# Sheet1.net
KiCad netlist of a schematic drawn in Altium Designer
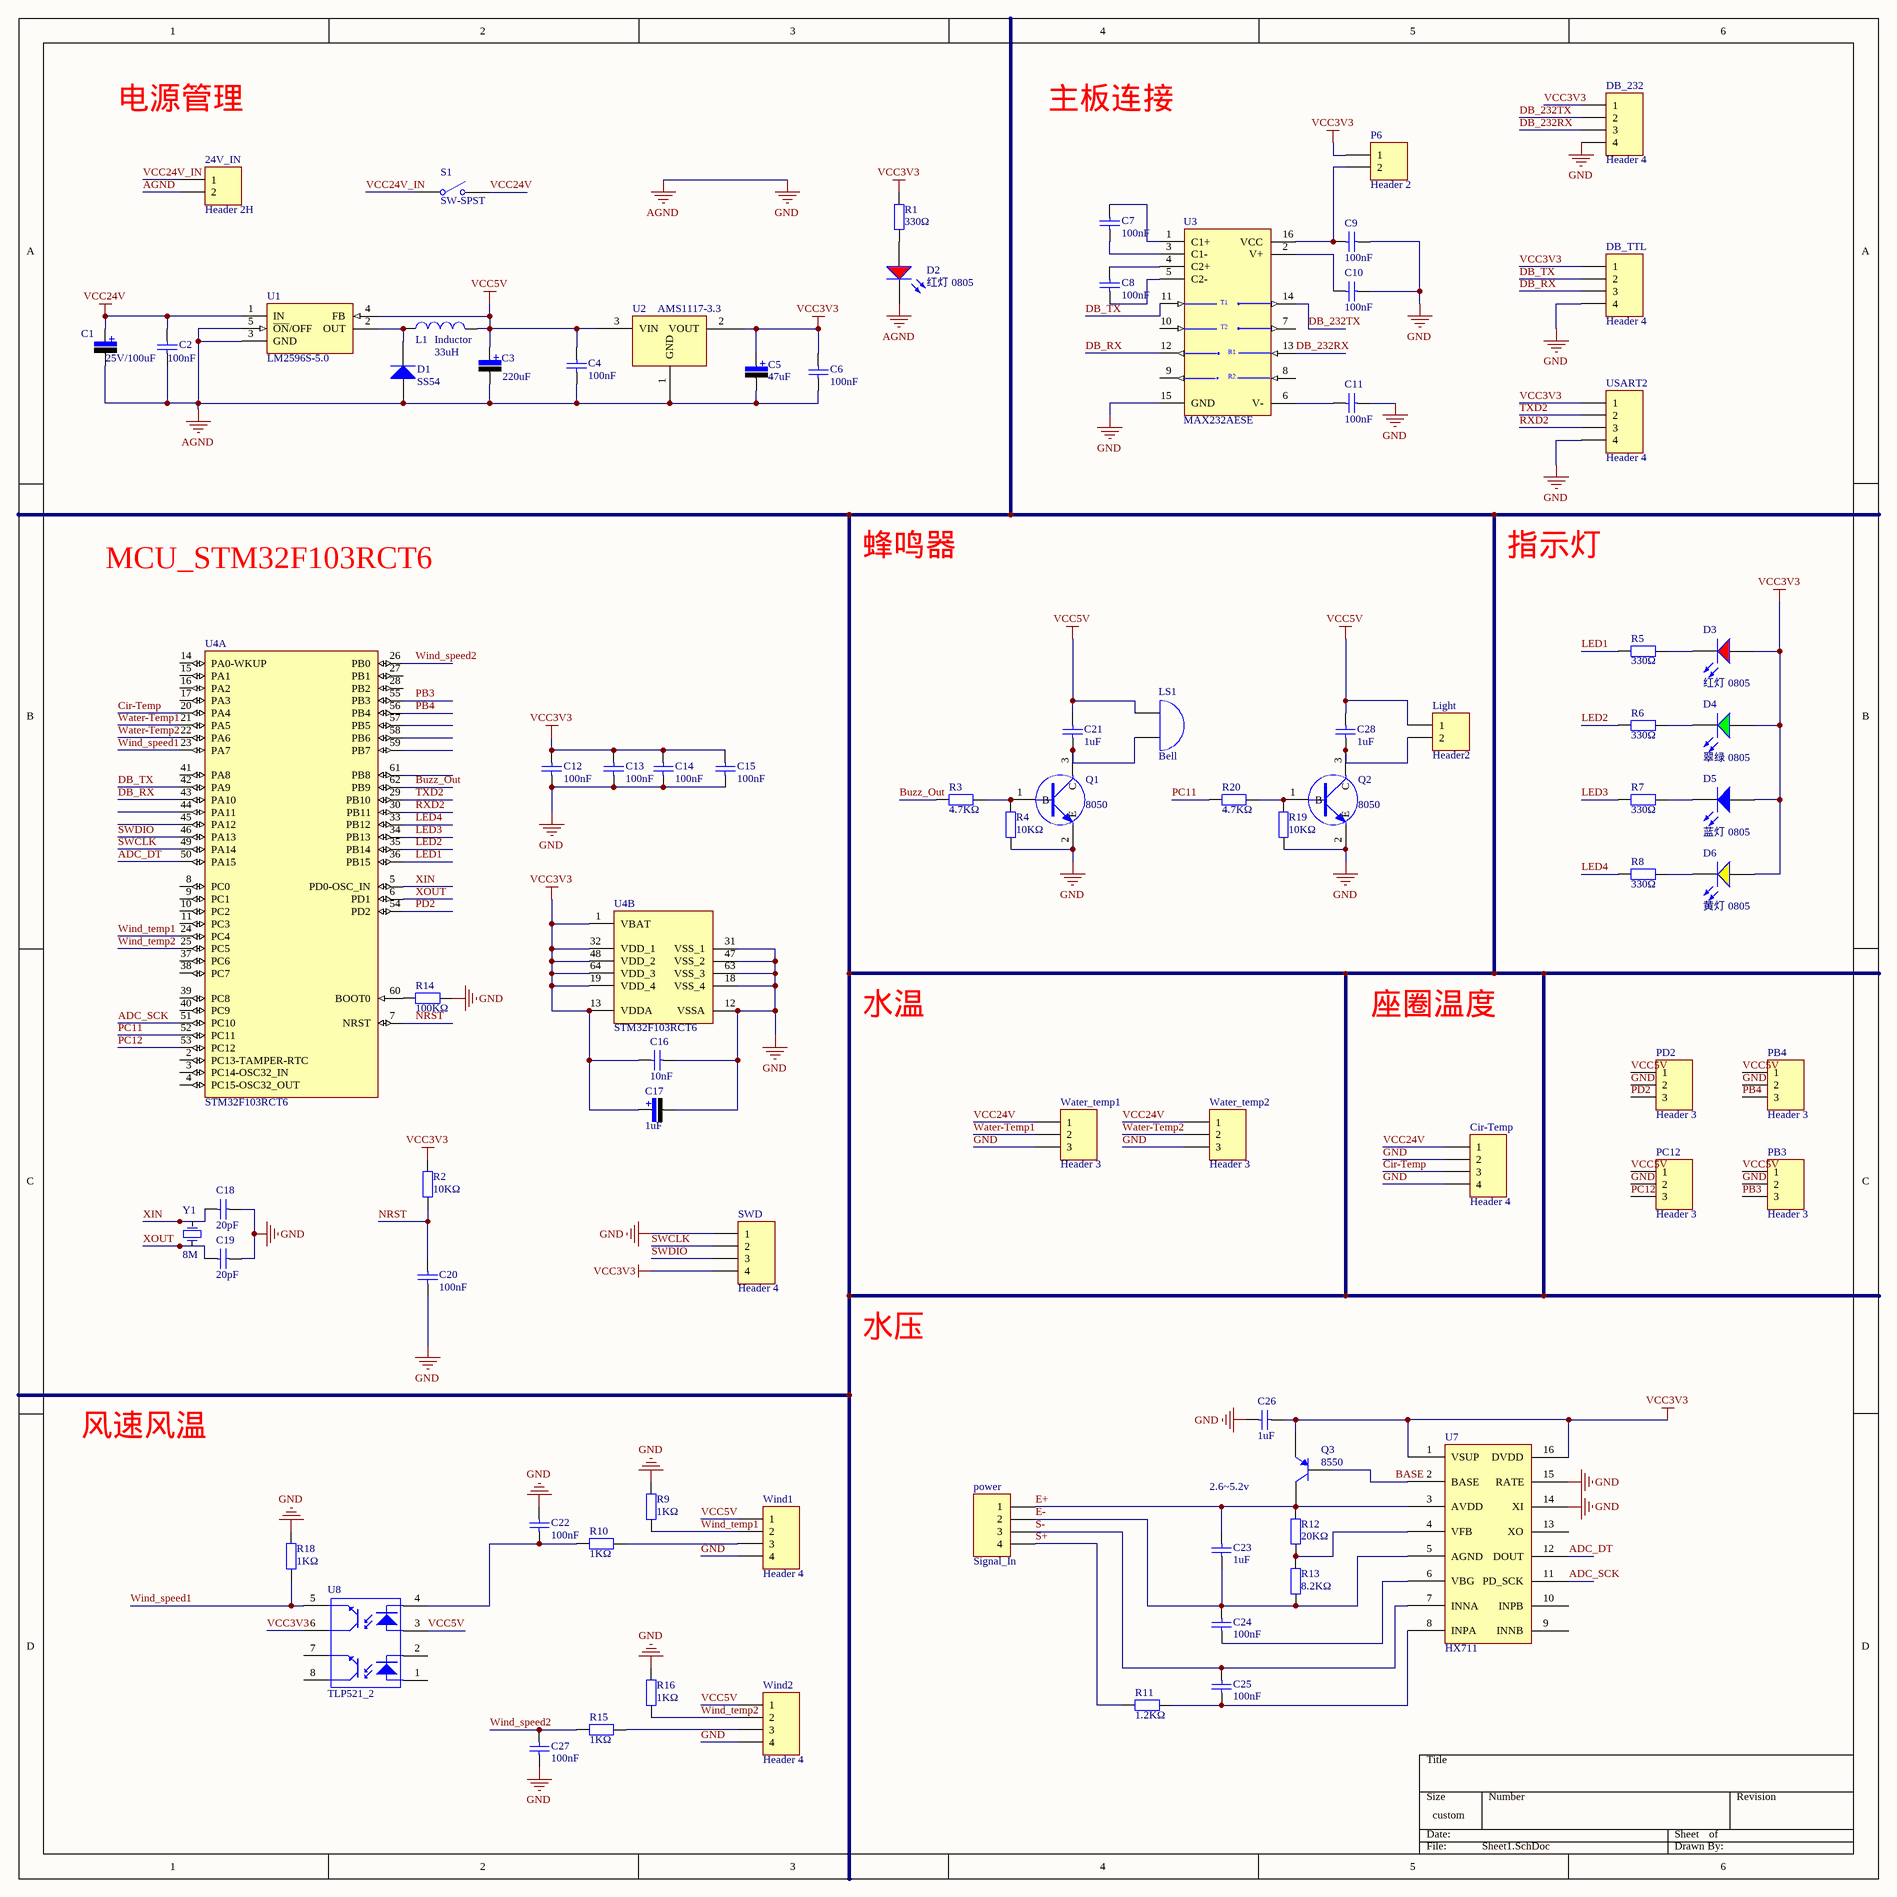
[diagram p0: Sheet1.SchDoc]

(export (version "E")
  (design (tool "Eeschema 10.0.6"))
  (components
    (comp (ref "24V_IN")
      (value "Header 2H")
      (footprint "4.2mm接插件2P")
      (description "Header, 2-Pin, Right Angle")
      (fields (field (name "PUBLISHER") "Altium Limited"))
      (libsource (lib "Miscellaneous Connectors") (part "Header 2H"))
    )
    (comp (ref "C1")
      (value "25V/100uF")
      (footprint "CC6.56.5")
      (description "极性电解电容")
      (fields (field (name "Comment") "Cap Pol") (field (name "PUBLISHER") "Altium Limited"))
      (libsource (lib "Cycle ergometer") (part "Cap Pol"))
    )
    (comp (ref "C2")
      (value "100nF")
      (footprint "0805_C")
      (description "贴片电容")
      (libsource (lib "Cap") (part "0805 100nF(104) 10% 50V"))
    )
    (comp (ref "C3")
      (value "220uF")
      (footprint "CC6.56.5")
      (description "极性电解电容")
      (fields (field (name "Comment") "Cap Pol") (field (name "PUBLISHER") "Altium Limited"))
      (libsource (lib "Cycle ergometer") (part "Cap Pol"))
    )
    (comp (ref "C4")
      (value "100nF")
      (footprint "0805_C")
      (description "贴片电容")
      (libsource (lib "Cap") (part "0805 100nF(104) 10% 50V"))
    )
    (comp (ref "C5")
      (value "47uF")
      (footprint "贴片电容5*5.4")
      (description "极性电解电容")
      (fields (field (name "Comment") "Cap Pol") (field (name "PUBLISHER") "Altium Limited"))
      (libsource (lib "Cycle ergometer") (part "Cap Pol"))
    )
    (comp (ref "C6")
      (value "100nF")
      (footprint "0805_C")
      (description "贴片电容")
      (libsource (lib "Cap") (part "0805 100nF(104) 10% 50V"))
    )
    (comp (ref "C7")
      (value "100nF")
      (footprint "0805_C")
      (description "贴片电容")
      (libsource (lib "Cap") (part "0805 100nF(104) 10% 50V"))
    )
    (comp (ref "C8")
      (value "100nF")
      (footprint "0805_C")
      (description "贴片电容")
      (libsource (lib "Cap") (part "0805 100nF(104) 10% 50V"))
    )
    (comp (ref "C9")
      (value "100nF")
      (footprint "0805_C")
      (description "贴片电容")
      (libsource (lib "Cap") (part "0805 100nF(104) 10% 50V"))
    )
    (comp (ref "C10")
      (value "100nF")
      (footprint "0805_C")
      (description "贴片电容")
      (libsource (lib "Cap") (part "0805 100nF(104) 10% 50V"))
    )
    (comp (ref "C11")
      (value "100nF")
      (footprint "0805_C")
      (description "贴片电容")
      (libsource (lib "Cap") (part "0805 100nF(104) 10% 50V"))
    )
    (comp (ref "C12")
      (value "100nF")
      (footprint "0805_C")
      (description "贴片电容")
      (libsource (lib "Cap") (part "0805 100nF(104) 10% 50V"))
    )
    (comp (ref "C13")
      (value "100nF")
      (footprint "0805_C")
      (description "贴片电容")
      (libsource (lib "Cap") (part "0805 100nF(104) 10% 50V"))
    )
    (comp (ref "C14")
      (value "100nF")
      (footprint "0805_C")
      (description "贴片电容")
      (libsource (lib "Cap") (part "0805 100nF(104) 10% 50V"))
    )
    (comp (ref "C15")
      (value "100nF")
      (footprint "0805_C")
      (description "贴片电容")
      (libsource (lib "Cap") (part "0805 100nF(104) 10% 50V"))
    )
    (comp (ref "C16")
      (value "10nF")
      (footprint "0805_C")
      (description "贴片电容")
      (libsource (lib "Cap") (part "0805 10nF (103) 10% 50V"))
    )
    (comp (ref "C17")
      (value "1uF")
      (footprint "贴片电容5*5.4")
      (description "极性电解电容")
      (fields (field (name "Comment") "Cap Pol") (field (name "PUBLISHER") "Altium Limited"))
      (libsource (lib "") (part "Cap Pol_1"))
    )
    (comp (ref "C18")
      (value "20pF")
      (footprint "0805_C")
      (description "贴片电容")
      (libsource (lib "Cap") (part "0805 20pF (200) 5% 50V"))
    )
    (comp (ref "C19")
      (value "20pF")
      (footprint "0805_C")
      (description "贴片电容")
      (libsource (lib "Cap") (part "0805 20pF (200) 5% 50V"))
    )
    (comp (ref "C20")
      (value "100nF")
      (footprint "0805_C")
      (description "贴片电容")
      (libsource (lib "Cap") (part "0805 100nF(104) 10% 50V"))
    )
    (comp (ref "C21")
      (value "1uF")
      (footprint "0805_C")
      (description "贴片电容")
      (libsource (lib "Cap-0805") (part "0805 1uF (105) 10% 50V"))
    )
    (comp (ref "C22")
      (value "100nF")
      (footprint "0805_C")
      (description "贴片电容")
      (libsource (lib "Cap-0805") (part "0805 100nF(104) 10% 50V"))
    )
    (comp (ref "C23")
      (value "1uF")
      (footprint "0805_C")
      (description "贴片电容")
      (libsource (lib "Cap-0805") (part "0805 1uF (105) 10% 50V"))
    )
    (comp (ref "C24")
      (value "100nF")
      (footprint "0805_C")
      (description "贴片电容")
      (libsource (lib "Cap-0805") (part "0805 100nF(104) 10% 50V"))
    )
    (comp (ref "C25")
      (value "100nF")
      (footprint "0805_C")
      (description "贴片电容")
      (libsource (lib "Cap-0805") (part "0805 100nF(104) 10% 50V"))
    )
    (comp (ref "C26")
      (value "1uF")
      (footprint "0805_C")
      (description "贴片电容")
      (libsource (lib "Cap-0805") (part "0805 1uF (105) 10% 50V"))
    )
    (comp (ref "C27")
      (value "100nF")
      (footprint "0805_C")
      (description "贴片电容")
      (libsource (lib "Cap-0805") (part "0805 100nF(104) 10% 50V"))
    )
    (comp (ref "C28")
      (value "1uF")
      (footprint "0805_C")
      (description "贴片电容")
      (libsource (lib "Cap-0805") (part "0805 1uF (105) 10% 50V"))
    )
    (comp (ref "Cir-Temp")
      (value "Header 4")
      (footprint "3.81MM-4P")
      (description "Header, 4-Pin")
      (fields (field (name "PUBLISHER") "Altium Limited"))
      (libsource (lib "") (part "Header 4_1"))
    )
    (comp (ref "D1")
      (value "SS54")
      (footprint "SMA(DO-214AC)_S1")
      (description "二极管")
      (libsource (lib "Diode") (part "SMA(DO-214AC) SS54"))
    )
    (comp (ref "D2")
      (value "红灯 0805")
      (footprint "0805_LED_S1")
      (description "发光二极管")
      (libsource (lib "LED") (part "0805 红灯"))
    )
    (comp (ref "D3")
      (value "红灯 0805")
      (footprint "0805_LED_S1")
      (description "发光二极管")
      (libsource (lib "LED") (part "0805 红灯"))
    )
    (comp (ref "D4")
      (value "翠绿 0805")
      (footprint "0805_LED_S1")
      (description "发光二极管")
      (libsource (lib "LED") (part "0805 翠绿"))
    )
    (comp (ref "D5")
      (value "蓝灯 0805")
      (footprint "0805_LED_S1")
      (description "发光二极管")
      (libsource (lib "LED") (part "0805 蓝灯"))
    )
    (comp (ref "D6")
      (value "黄灯 0805")
      (footprint "0805_LED_S1")
      (description "发光二极管")
      (libsource (lib "LED") (part "0805 黄灯"))
    )
    (comp (ref "DB_232")
      (value "Header 4")
      (footprint "3.81MM-4P")
      (description "Header, 4-Pin")
      (fields (field (name "PUBLISHER") "Altium Limited"))
      (libsource (lib "") (part "Header 4_1"))
    )
    (comp (ref "DB_TTL")
      (value "Header 4")
      (footprint "3.81MM-4P")
      (description "Header, 4-Pin")
      (fields (field (name "PUBLISHER") "Altium Limited"))
      (libsource (lib "") (part "Header 4_1"))
    )
    (comp (ref "L1")
      (value "Inductor")
      (footprint "功率电感7*7")
      (fields (field (name "ALTIUM_VALUE") "33uH") (field (name "PUBLISHER") "Altium Limited"))
      (libsource (lib "Miscellaneous Devices") (part "Inductor"))
    )
    (comp (ref "Light")
      (value "Header2")
      (footprint "3.81mm-2P")
      (description "Header, 2-Pin")
      (fields (field (name "PUBLISHER") "Altium Limited"))
      (libsource (lib "Free Documents") (part "Header 2"))
    )
    (comp (ref "LS1")
      (value "Bell")
      (footprint "有源蜂鸣器5V")
      (description "Electrical Bell")
      (fields (field (name "PUBLISHER") "Altium Limited"))
      (libsource (lib "Miscellaneous Devices") (part "Bell"))
    )
    (comp (ref "P6")
      (value "Header 2")
      (footprint "HDR1X2")
      (description "Header, 2-Pin")
      (fields (field (name "PUBLISHER") "Altium Limited"))
      (libsource (lib "Miscellaneous Connectors") (part "Header 2"))
    )
    (comp (ref "PB3")
      (value "Header 3")
      (footprint "HDR1X3")
      (description "Header, 3-Pin")
      (fields (field (name "PUBLISHER") "Altium Limited"))
      (libsource (lib "Free Documents") (part "Header 3"))
    )
    (comp (ref "PB4")
      (value "Header 3")
      (footprint "HDR1X3")
      (description "Header, 3-Pin")
      (fields (field (name "PUBLISHER") "Altium Limited"))
      (libsource (lib "Free Documents") (part "Header 3"))
    )
    (comp (ref "PC12")
      (value "Header 3")
      (footprint "HDR1X3")
      (description "Header, 3-Pin")
      (fields (field (name "PUBLISHER") "Altium Limited"))
      (libsource (lib "Free Documents") (part "Header 3"))
    )
    (comp (ref "PD2")
      (value "Header 3")
      (footprint "HDR1X3")
      (description "Header, 3-Pin")
      (fields (field (name "PUBLISHER") "Altium Limited"))
      (libsource (lib "Free Documents") (part "Header 3"))
    )
    (comp (ref "power")
      (value "Signal_In")
      (footprint "3.81MM-4P")
      (description "Header, 4-Pin")
      (fields (field (name "PUBLISHER") "Altium Limited"))
      (libsource (lib "Miscellaneous Connectors") (part "Header 4"))
    )
    (comp (ref "Q1") (value "8050") (footprint "SOT-23_3C") (libsource (lib "*") (part "NPN(1)")))
    (comp (ref "Q2") (value "8050") (footprint "SOT-23_3C") (libsource (lib "*") (part "NPN(1)")))
    (comp (ref "Q3") (value "8550") (footprint "SOT23A") (libsource (lib "hx711") (part "pnp8550")))
    (comp (ref "R1")
      (value "330Ω")
      (footprint "0805_R")
      (description "贴片电阻")
      (libsource (lib "RES") (part "0805 330Ω (3300) 1%"))
    )
    (comp (ref "R2")
      (value "10KΩ")
      (footprint "0805_R")
      (description "贴片电阻")
      (libsource (lib "RES") (part "0805 10KΩ (1002) 1%"))
    )
    (comp (ref "R3")
      (value "4.7KΩ")
      (footprint "0805_R")
      (description "贴片电阻")
      (libsource (lib "RES-0805") (part "0805 4.7KΩ (4701) 1%"))
    )
    (comp (ref "R4")
      (value "10KΩ")
      (footprint "0805_R")
      (description "贴片电阻")
      (libsource (lib "RES-0805") (part "0805 10KΩ (1002) 1%"))
    )
    (comp (ref "R5")
      (value "330Ω")
      (footprint "0805_R")
      (description "贴片电阻")
      (libsource (lib "RES-0805") (part "0805 330Ω (3300) 1%"))
    )
    (comp (ref "R6")
      (value "330Ω")
      (footprint "0805_R")
      (description "贴片电阻")
      (libsource (lib "RES-0805") (part "0805 330Ω (3300) 1%"))
    )
    (comp (ref "R7")
      (value "330Ω")
      (footprint "0805_R")
      (description "贴片电阻")
      (libsource (lib "RES-0805") (part "0805 330Ω (3300) 1%"))
    )
    (comp (ref "R8")
      (value "330Ω")
      (footprint "0805_R")
      (description "贴片电阻")
      (libsource (lib "RES-0805") (part "0805 330Ω (3300) 1%"))
    )
    (comp (ref "R9")
      (value "1KΩ")
      (footprint "0805_R")
      (description "贴片电阻")
      (libsource (lib "") (part "0805 1KΩ (1001) 1%_1"))
    )
    (comp (ref "R10")
      (value "1KΩ")
      (footprint "0805_R")
      (description "贴片电阻")
      (libsource (lib "RES-0805") (part "0805 1KΩ (1001) 1%"))
    )
    (comp (ref "R11")
      (value "1.2KΩ")
      (footprint "0805_R")
      (description "贴片电阻")
      (libsource (lib "RES-0805") (part "0805 1.2KΩ (1201) 1%"))
    )
    (comp (ref "R12")
      (value "20KΩ")
      (footprint "0805_R")
      (description "贴片电阻")
      (libsource (lib "RES-0805") (part "0805 20KΩ (2002) 1%"))
    )
    (comp (ref "R13")
      (value "8.2KΩ")
      (footprint "0805_R")
      (description "贴片电阻")
      (libsource (lib "RES-0805") (part "0805 8.2KΩ (8201) 1%"))
    )
    (comp (ref "R14")
      (value "100KΩ")
      (footprint "0805_R")
      (description "贴片电阻")
      (libsource (lib "RES-0805") (part "0805 100KΩ (1003) 1%"))
    )
    (comp (ref "R15")
      (value "1KΩ")
      (footprint "0805_R")
      (description "贴片电阻")
      (libsource (lib "RES-0805") (part "0805 1KΩ (1001) 1%"))
    )
    (comp (ref "R16")
      (value "1KΩ")
      (footprint "0805_R")
      (description "贴片电阻")
      (libsource (lib "") (part "0805 1KΩ (1001) 1%_1"))
    )
    (comp (ref "R18")
      (value "1KΩ")
      (footprint "0805_R")
      (description "贴片电阻")
      (libsource (lib "") (part "0805 1KΩ (1001) 1%_1"))
    )
    (comp (ref "R19")
      (value "10KΩ")
      (footprint "0805_R")
      (description "贴片电阻")
      (libsource (lib "RES-0805") (part "0805 10KΩ (1002) 1%"))
    )
    (comp (ref "R20")
      (value "4.7KΩ")
      (footprint "0805_R")
      (description "贴片电阻")
      (libsource (lib "RES-0805") (part "0805 4.7KΩ (4701) 1%"))
    )
    (comp (ref "S1")
      (value "SW-SPST")
      (footprint "纽子开关")
      (description "Single-Pole, Single-Throw Switch")
      (fields (field (name "PUBLISHER") "Altium Limited"))
      (libsource (lib "Miscellaneous Devices") (part "SW-SPST"))
    )
    (comp (ref "SWD")
      (value "Header 4")
      (footprint "HDR1X4")
      (description "Header, 4-Pin")
      (fields (field (name "PUBLISHER") "Altium Limited"))
      (libsource (lib "") (part "Header 4_1"))
    )
    (comp (ref "U1")
      (value "LM2596S-5.0")
      (footprint "TO-263-5L(D2PAK)")
      (description "Simple Switcher Power Converter 150 kHz 3A Step Down Voltage Regulator")
      (fields (field (name "PUBLISHER") "Altium Limited"))
      (libsource (lib "NSC Power Mgt Switching Regulator") (part "LM2596S-5.0"))
    )
    (comp (ref "U2") (value "AMS1117-3.3") (footprint "SOT223") (libsource (lib "mctrl") (part "AS1117")))
    (comp (ref "U3")
      (value "MAX232AESE")
      (footprint "L16_L")
      (description "+5V-Powered, Multichannel RS-232 Driver/Receiver")
      (fields (field (name "PUBLISHER") "Altium Limited"))
      (libsource (lib "Maxim Communication Transceiver") (part "MAX232AESE"))
    )
    (comp (ref "U4")
      (value "STM32F103RCT6")
      (footprint "LQFP-64_10x10x05P")
      (description "ARM")
      (libsource (lib "MCU") (part "STM32F103RCT6"))
    )
    (comp (ref "U7")
      (value "HX711")
      (footprint "HX711_增加引脚长度")
      (description "24 位 A/D 转 换器芯片，集成稳压电源、片内时钟振荡器等")
      (libsource (lib "hx711") (part "HX711"))
    )
    (comp (ref "U8")
      (value "TLP521_2")
      (footprint "TLP521-2")
      (libsource (lib "Free Documents") (part "TLP521_2"))
    )
    (comp (ref "USART2")
      (value "Header 4")
      (footprint "3.81MM-4P")
      (description "Header, 4-Pin")
      (fields (field (name "PUBLISHER") "Altium Limited"))
      (libsource (lib "") (part "Header 4_1"))
    )
    (comp (ref "Water_temp1")
      (value "Header 3")
      (footprint "3.81mm-3P")
      (description "Header, 3-Pin")
      (fields (field (name "PUBLISHER") "Altium Limited"))
      (libsource (lib "Free Documents") (part "Header 3"))
    )
    (comp (ref "Water_temp2")
      (value "Header 3")
      (footprint "3.81mm-3P")
      (description "Header, 3-Pin")
      (fields (field (name "PUBLISHER") "Altium Limited"))
      (libsource (lib "Free Documents") (part "Header 3"))
    )
    (comp (ref "Wind1")
      (value "Header 4")
      (footprint "3.81MM-4P")
      (description "Header, 4-Pin")
      (fields (field (name "PUBLISHER") "Altium Limited"))
      (libsource (lib "") (part "Header 4_1"))
    )
    (comp (ref "Wind2")
      (value "Header 4")
      (footprint "3.81MM-4P")
      (description "Header, 4-Pin")
      (fields (field (name "PUBLISHER") "Altium Limited"))
      (libsource (lib "") (part "Header 4_1"))
    )
    (comp (ref "Y1")
      (value "8M")
      (footprint "X-HC49U")
      (description "晶振")
      (fields (field (name "Comment") "XTAL") (field (name "PUBLISHER") "Altium Limited"))
      (libsource (lib "Cycle ergometer") (part "XTAL"))
    )
  )
  (nets
    (net (code "1") (name "/ADC_DT") (class "Default")
      (node (ref "U4") (pin "50") (pinfunction "PA15_50") (pintype "bidirectional"))
      (node (ref "U7") (pin "12") (pinfunction "DOUT_12") (pintype "passive"))
    )
    (net (code "2") (name "/ADC_SCK") (class "Default")
      (node (ref "U4") (pin "51") (pinfunction "PC10_51") (pintype "bidirectional"))
      (node (ref "U7") (pin "11") (pinfunction "PD_SCK_11") (pintype "passive"))
    )
    (net (code "3") (name "/BASE") (class "Default")
      (node (ref "Q3") (pin "1") (pinfunction "B_1") (pintype "passive"))
      (node (ref "U7") (pin "2") (pinfunction "BASE_2") (pintype "passive"))
    )
    (net (code "4") (name "/Buzz_Out") (class "Default")
      (node (ref "R3") (pin "1") (pinfunction "1_1") (pintype "passive"))
      (node (ref "U4") (pin "62") (pinfunction "PB9_62") (pintype "bidirectional"))
    )
    (net (code "5") (name "/Cir-Temp") (class "Default")
      (node (ref "Cir-Temp") (pin "3") (pinfunction "3_3") (pintype "passive"))
      (node (ref "U4") (pin "20") (pinfunction "PA4_20") (pintype "bidirectional"))
    )
    (net (code "6") (name "/DB_232RX") (class "Default")
      (node (ref "DB_232") (pin "3") (pinfunction "3_3") (pintype "passive"))
      (node (ref "U3") (pin "13") (pinfunction "R1IN_13") (pintype "input"))
    )
    (net (code "7") (name "/DB_232TX") (class "Default")
      (node (ref "DB_232") (pin "2") (pinfunction "2_2") (pintype "passive"))
      (node (ref "U3") (pin "14") (pinfunction "T1OUT_14") (pintype "output"))
    )
    (net (code "8") (name "/DB_RX") (class "Default")
      (node (ref "DB_TTL") (pin "3") (pinfunction "3_3") (pintype "passive"))
      (node (ref "U3") (pin "12") (pinfunction "R1OUT_12") (pintype "output"))
      (node (ref "U4") (pin "43") (pinfunction "PA10_43") (pintype "bidirectional"))
    )
    (net (code "9") (name "/DB_TX") (class "Default")
      (node (ref "DB_TTL") (pin "2") (pinfunction "2_2") (pintype "passive"))
      (node (ref "U3") (pin "11") (pinfunction "T1IN_11") (pintype "input"))
      (node (ref "U4") (pin "42") (pinfunction "PA9_42") (pintype "bidirectional"))
    )
    (net (code "10") (name "/E+") (class "Default")
      (node (ref "C23") (pin "2") (pinfunction "2_2") (pintype "passive"))
      (node (ref "Q3") (pin "3") (pinfunction "C_3") (pintype "passive"))
      (node (ref "R12") (pin "2") (pinfunction "2_2") (pintype "passive"))
      (node (ref "U7") (pin "3") (pinfunction "AVDD_3") (pintype "passive"))
      (node (ref "power") (pin "1") (pinfunction "1_1") (pintype "passive"))
    )
    (net (code "11") (name "/E-") (class "Default")
      (node (ref "C23") (pin "1") (pinfunction "1_1") (pintype "passive"))
      (node (ref "C24") (pin "2") (pinfunction "2_2") (pintype "passive"))
      (node (ref "R13") (pin "1") (pinfunction "1_1") (pintype "passive"))
      (node (ref "U7") (pin "5") (pinfunction "AGND_5") (pintype "passive"))
      (node (ref "power") (pin "2") (pinfunction "2_2") (pintype "passive"))
    )
    (net (code "12") (name "/LED1") (class "Default")
      (node (ref "R5") (pin "1") (pinfunction "1_1") (pintype "passive"))
      (node (ref "U4") (pin "36") (pinfunction "PB15_36") (pintype "bidirectional"))
    )
    (net (code "13") (name "/LED2") (class "Default")
      (node (ref "R6") (pin "1") (pinfunction "1_1") (pintype "passive"))
      (node (ref "U4") (pin "35") (pinfunction "PB14_35") (pintype "bidirectional"))
    )
    (net (code "14") (name "/LED3") (class "Default")
      (node (ref "R7") (pin "1") (pinfunction "1_1") (pintype "passive"))
      (node (ref "U4") (pin "34") (pinfunction "PB13_34") (pintype "bidirectional"))
    )
    (net (code "15") (name "/LED4") (class "Default")
      (node (ref "R8") (pin "1") (pinfunction "1_1") (pintype "passive"))
      (node (ref "U4") (pin "33") (pinfunction "PB12_33") (pintype "bidirectional"))
    )
    (net (code "16") (name "/NRST") (class "Default")
      (node (ref "C20") (pin "2") (pinfunction "2_2") (pintype "passive"))
      (node (ref "R2") (pin "1") (pinfunction "1_1") (pintype "passive"))
      (node (ref "U4") (pin "7") (pinfunction "NRST_7") (pintype "bidirectional"))
    )
    (net (code "17") (name "/PB3") (class "Default")
      (node (ref "PB3") (pin "3") (pinfunction "3_3") (pintype "passive"))
      (node (ref "U4") (pin "55") (pinfunction "PB3_55") (pintype "bidirectional"))
    )
    (net (code "18") (name "/PB4") (class "Default")
      (node (ref "PB4") (pin "3") (pinfunction "3_3") (pintype "passive"))
      (node (ref "U4") (pin "56") (pinfunction "PB4_56") (pintype "bidirectional"))
    )
    (net (code "19") (name "/PC11") (class "Default")
      (node (ref "R20") (pin "1") (pinfunction "1_1") (pintype "passive"))
      (node (ref "U4") (pin "52") (pinfunction "PC11_52") (pintype "bidirectional"))
    )
    (net (code "20") (name "/PC12") (class "Default")
      (node (ref "PC12") (pin "3") (pinfunction "3_3") (pintype "passive"))
      (node (ref "U4") (pin "53") (pinfunction "PC12_53") (pintype "bidirectional"))
    )
    (net (code "21") (name "/PD2") (class "Default")
      (node (ref "PD2") (pin "3") (pinfunction "3_3") (pintype "passive"))
      (node (ref "U4") (pin "54") (pinfunction "PD2_54") (pintype "bidirectional"))
    )
    (net (code "22") (name "/RXD2") (class "Default")
      (node (ref "U4") (pin "30") (pinfunction "PB11_30") (pintype "bidirectional"))
      (node (ref "USART2") (pin "3") (pinfunction "3_3") (pintype "passive"))
    )
    (net (code "23") (name "/S+") (class "Default")
      (node (ref "R11") (pin "1") (pinfunction "1_1") (pintype "passive"))
      (node (ref "power") (pin "4") (pinfunction "4_4") (pintype "passive"))
    )
    (net (code "24") (name "/S-") (class "Default")
      (node (ref "C25") (pin "2") (pinfunction "2_2") (pintype "passive"))
      (node (ref "U7") (pin "7") (pinfunction "INNA_7") (pintype "passive"))
      (node (ref "power") (pin "3") (pinfunction "3_3") (pintype "passive"))
    )
    (net (code "25") (name "/SWCLK") (class "Default")
      (node (ref "SWD") (pin "2") (pinfunction "2_2") (pintype "passive"))
      (node (ref "U4") (pin "49") (pinfunction "PA14_49") (pintype "bidirectional"))
    )
    (net (code "26") (name "/SWDIO") (class "Default")
      (node (ref "SWD") (pin "3") (pinfunction "3_3") (pintype "passive"))
      (node (ref "U4") (pin "46") (pinfunction "PA13_46") (pintype "bidirectional"))
    )
    (net (code "27") (name "/TXD2") (class "Default")
      (node (ref "U4") (pin "29") (pinfunction "PB10_29") (pintype "bidirectional"))
      (node (ref "USART2") (pin "2") (pinfunction "2_2") (pintype "passive"))
    )
    (net (code "28") (name "/VCC24V_IN") (class "Default")
      (node (ref "24V_IN") (pin "1") (pinfunction "1_1") (pintype "passive"))
      (node (ref "S1") (pin "1") (pinfunction "COMMON_1") (pintype "passive"))
    )
    (net (code "29") (name "/Water-Temp1") (class "Default")
      (node (ref "U4") (pin "21") (pinfunction "PA5_21") (pintype "bidirectional"))
      (node (ref "Water_temp1") (pin "2") (pinfunction "2_2") (pintype "passive"))
    )
    (net (code "30") (name "/Water-Temp2") (class "Default")
      (node (ref "U4") (pin "22") (pinfunction "PA6_22") (pintype "bidirectional"))
      (node (ref "Water_temp2") (pin "2") (pinfunction "2_2") (pintype "passive"))
    )
    (net (code "31") (name "/Wind_speed1") (class "Default")
      (node (ref "R18") (pin "1") (pinfunction "1_1") (pintype "passive"))
      (node (ref "U4") (pin "23") (pinfunction "PA7_23") (pintype "bidirectional"))
      (node (ref "U8") (pin "5") (pinfunction "E_5") (pintype "passive"))
    )
    (net (code "32") (name "/Wind_speed2") (class "Default")
      (node (ref "C27") (pin "2") (pinfunction "2_2") (pintype "passive"))
      (node (ref "R15") (pin "1") (pinfunction "1_1") (pintype "passive"))
      (node (ref "U4") (pin "26") (pinfunction "PB0_26") (pintype "bidirectional"))
    )
    (net (code "33") (name "/Wind_temp1") (class "Default")
      (node (ref "R9") (pin "1") (pinfunction "1_1") (pintype "passive"))
      (node (ref "U4") (pin "24") (pinfunction "PC4_24") (pintype "bidirectional"))
      (node (ref "Wind1") (pin "2") (pinfunction "2_2") (pintype "passive"))
    )
    (net (code "34") (name "/Wind_temp2") (class "Default")
      (node (ref "R16") (pin "1") (pinfunction "1_1") (pintype "passive"))
      (node (ref "U4") (pin "25") (pinfunction "PC5_25") (pintype "bidirectional"))
      (node (ref "Wind2") (pin "2") (pinfunction "2_2") (pintype "passive"))
    )
    (net (code "35") (name "/XIN") (class "Default")
      (node (ref "C18") (pin "1") (pinfunction "1_1") (pintype "passive"))
      (node (ref "U4") (pin "5") (pinfunction "PD0-OSC_IN_5") (pintype "bidirectional"))
      (node (ref "Y1") (pin "1") (pinfunction "OSC1_1") (pintype "passive"))
    )
    (net (code "36") (name "/XOUT") (class "Default")
      (node (ref "C19") (pin "1") (pinfunction "1_1") (pintype "passive"))
      (node (ref "U4") (pin "6") (pinfunction "PD1_6") (pintype "bidirectional"))
      (node (ref "Y1") (pin "2") (pinfunction "OSC2_2") (pintype "passive"))
    )
    (net (code "37") (name "AGND") (class "Default")
      (node (ref "24V_IN") (pin "2") (pinfunction "2_2") (pintype "passive"))
      (node (ref "C1") (pin "2") (pinfunction "2_2") (pintype "passive"))
      (node (ref "C10") (pin "1") (pinfunction "1_1") (pintype "passive"))
      (node (ref "C11") (pin "1") (pinfunction "1_1") (pintype "passive"))
      (node (ref "C12") (pin "1") (pinfunction "1_1") (pintype "passive"))
      (node (ref "C13") (pin "1") (pinfunction "1_1") (pintype "passive"))
      (node (ref "C14") (pin "1") (pinfunction "1_1") (pintype "passive"))
      (node (ref "C15") (pin "1") (pinfunction "1_1") (pintype "passive"))
      (node (ref "C16") (pin "2") (pinfunction "2_2") (pintype "passive"))
      (node (ref "C17") (pin "2") (pinfunction "2_2") (pintype "passive"))
      (node (ref "C18") (pin "2") (pinfunction "2_2") (pintype "passive"))
      (node (ref "C19") (pin "2") (pinfunction "2_2") (pintype "passive"))
      (node (ref "C2") (pin "1") (pinfunction "1_1") (pintype "passive"))
      (node (ref "C20") (pin "1") (pinfunction "1_1") (pintype "passive"))
      (node (ref "C22") (pin "1") (pinfunction "1_1") (pintype "passive"))
      (node (ref "C26") (pin "2") (pinfunction "2_2") (pintype "passive"))
      (node (ref "C27") (pin "1") (pinfunction "1_1") (pintype "passive"))
      (node (ref "C3") (pin "2") (pinfunction "2_2") (pintype "passive"))
      (node (ref "C4") (pin "1") (pinfunction "1_1") (pintype "passive"))
      (node (ref "C5") (pin "2") (pinfunction "2_2") (pintype "passive"))
      (node (ref "C6") (pin "1") (pinfunction "1_1") (pintype "passive"))
      (node (ref "C9") (pin "1") (pinfunction "1_1") (pintype "passive"))
      (node (ref "Cir-Temp") (pin "2") (pinfunction "2_2") (pintype "passive"))
      (node (ref "Cir-Temp") (pin "4") (pinfunction "4_4") (pintype "passive"))
      (node (ref "D1") (pin "1") (pinfunction "A_1") (pintype "passive"))
      (node (ref "D2") (pin "K") (pinfunction "K_K") (pintype "passive"))
      (node (ref "DB_232") (pin "4") (pinfunction "4_4") (pintype "passive"))
      (node (ref "DB_TTL") (pin "4") (pinfunction "4_4") (pintype "passive"))
      (node (ref "PB3") (pin "2") (pinfunction "2_2") (pintype "passive"))
      (node (ref "PB4") (pin "2") (pinfunction "2_2") (pintype "passive"))
      (node (ref "PC12") (pin "2") (pinfunction "2_2") (pintype "passive"))
      (node (ref "PD2") (pin "2") (pinfunction "2_2") (pintype "passive"))
      (node (ref "Q1") (pin "2") (pinfunction "E_2") (pintype "passive"))
      (node (ref "Q2") (pin "2") (pinfunction "E_2") (pintype "passive"))
      (node (ref "R14") (pin "2") (pinfunction "2_2") (pintype "passive"))
      (node (ref "R16") (pin "2") (pinfunction "2_2") (pintype "passive"))
      (node (ref "R18") (pin "2") (pinfunction "2_2") (pintype "passive"))
      (node (ref "R19") (pin "1") (pinfunction "1_1") (pintype "passive"))
      (node (ref "R4") (pin "1") (pinfunction "1_1") (pintype "passive"))
      (node (ref "R9") (pin "2") (pinfunction "2_2") (pintype "passive"))
      (node (ref "SWD") (pin "1") (pinfunction "1_1") (pintype "passive"))
      (node (ref "U1") (pin "3") (pinfunction "GND_3") (pintype "power_in"))
      (node (ref "U1") (pin "5") (pinfunction "~{ON}/OFF_5") (pintype "input"))
      (node (ref "U2") (pin "1") (pinfunction "GND_1") (pintype "passive"))
      (node (ref "U3") (pin "15") (pinfunction "GND_15") (pintype "power_in"))
      (node (ref "U4") (pin "12") (pinfunction "VSSA_12") (pintype "power_in"))
      (node (ref "U4") (pin "18") (pinfunction "VSS_4_18") (pintype "power_in"))
      (node (ref "U4") (pin "31") (pinfunction "VSS_1_31") (pintype "power_in"))
      (node (ref "U4") (pin "47") (pinfunction "VSS_2_47") (pintype "power_in"))
      (node (ref "U4") (pin "63") (pinfunction "VSS_3_63") (pintype "power_in"))
      (node (ref "U7") (pin "14") (pinfunction "XI_14") (pintype "passive"))
      (node (ref "U7") (pin "15") (pinfunction "RATE_15") (pintype "passive"))
      (node (ref "USART2") (pin "4") (pinfunction "4_4") (pintype "passive"))
      (node (ref "Water_temp1") (pin "3") (pinfunction "3_3") (pintype "passive"))
      (node (ref "Water_temp2") (pin "3") (pinfunction "3_3") (pintype "passive"))
      (node (ref "Wind1") (pin "4") (pinfunction "4_4") (pintype "passive"))
      (node (ref "Wind2") (pin "4") (pinfunction "4_4") (pintype "passive"))
    )
    (net (code "38") (name "Net-(C22-Pad2)") (class "Default")
      (node (ref "C22") (pin "2") (pinfunction "2_2") (pintype "passive"))
      (node (ref "R10") (pin "1") (pinfunction "1_1") (pintype "passive"))
      (node (ref "U8") (pin "4") (pinfunction "K_4") (pintype "passive"))
    )
    (net (code "39") (name "Net-(D1-K)") (class "Default")
      (node (ref "D1") (pin "2") (pinfunction "K_2") (pintype "passive"))
      (node (ref "L1") (pin "1") (pinfunction "1_1") (pintype "passive"))
      (node (ref "U1") (pin "2") (pinfunction "OUT_2") (pintype "power_in"))
    )
    (net (code "40") (name "Net-(D2-PadA)") (class "Default")
      (node (ref "D2") (pin "A") (pinfunction "A_A") (pintype "passive"))
      (node (ref "R1") (pin "1") (pinfunction "1_1") (pintype "passive"))
    )
    (net (code "41") (name "Net-(D3-PadK)") (class "Default")
      (node (ref "D3") (pin "K") (pinfunction "K_K") (pintype "passive"))
      (node (ref "R5") (pin "2") (pinfunction "2_2") (pintype "passive"))
    )
    (net (code "42") (name "Net-(D4-PadK)") (class "Default")
      (node (ref "D4") (pin "K") (pinfunction "K_K") (pintype "passive"))
      (node (ref "R6") (pin "2") (pinfunction "2_2") (pintype "passive"))
    )
    (net (code "43") (name "Net-(D5-PadK)") (class "Default")
      (node (ref "D5") (pin "K") (pinfunction "K_K") (pintype "passive"))
      (node (ref "R7") (pin "2") (pinfunction "2_2") (pintype "passive"))
    )
    (net (code "44") (name "Net-(D6-PadK)") (class "Default")
      (node (ref "D6") (pin "K") (pinfunction "K_K") (pintype "passive"))
      (node (ref "R8") (pin "2") (pinfunction "2_2") (pintype "passive"))
    )
    (net (code "45") (name "Net-(LS1-B)") (class "Default")
      (node (ref "C21") (pin "1") (pinfunction "1_1") (pintype "passive"))
      (node (ref "LS1") (pin "2") (pinfunction "B_2") (pintype "passive"))
      (node (ref "Q1") (pin "3") (pinfunction "C_3") (pintype "passive"))
    )
    (net (code "46") (name "Net-(Q1-B)") (class "Default")
      (node (ref "Q1") (pin "1") (pinfunction "B_1") (pintype "passive"))
      (node (ref "R3") (pin "2") (pinfunction "2_2") (pintype "passive"))
      (node (ref "R4") (pin "2") (pinfunction "2_2") (pintype "passive"))
    )
    (net (code "47") (name "Net-(Q2-B)") (class "Default")
      (node (ref "Q2") (pin "1") (pinfunction "B_1") (pintype "passive"))
      (node (ref "R19") (pin "2") (pinfunction "2_2") (pintype "passive"))
      (node (ref "R20") (pin "2") (pinfunction "2_2") (pintype "passive"))
    )
    (net (code "48") (name "Net-(Q2-C)") (class "Default")
      (node (ref "C28") (pin "1") (pinfunction "1_1") (pintype "passive"))
      (node (ref "Light") (pin "2") (pinfunction "2_2") (pintype "passive"))
      (node (ref "Q2") (pin "3") (pinfunction "C_3") (pintype "passive"))
    )
    (net (code "49") (name "Net-(R10-Pad2)") (class "Default")
      (node (ref "R10") (pin "2") (pinfunction "2_2") (pintype "passive"))
      (node (ref "Wind1") (pin "3") (pinfunction "3_3") (pintype "passive"))
    )
    (net (code "50") (name "Net-(R15-Pad2)") (class "Default")
      (node (ref "R15") (pin "2") (pinfunction "2_2") (pintype "passive"))
      (node (ref "Wind2") (pin "3") (pinfunction "3_3") (pintype "passive"))
    )
    (net (code "51") (name "Net-(U3-C1+)") (class "Default")
      (node (ref "C7") (pin "2") (pinfunction "2_2") (pintype "passive"))
      (node (ref "U3") (pin "1") (pinfunction "C1+_1") (pintype "passive"))
    )
    (net (code "52") (name "Net-(U3-C1-)") (class "Default")
      (node (ref "C7") (pin "1") (pinfunction "1_1") (pintype "passive"))
      (node (ref "U3") (pin "3") (pinfunction "C1-_3") (pintype "passive"))
    )
    (net (code "53") (name "Net-(U3-C2+)") (class "Default")
      (node (ref "C8") (pin "2") (pinfunction "2_2") (pintype "passive"))
      (node (ref "U3") (pin "4") (pinfunction "C2+_4") (pintype "passive"))
    )
    (net (code "54") (name "Net-(U3-C2-)") (class "Default")
      (node (ref "C8") (pin "1") (pinfunction "1_1") (pintype "passive"))
      (node (ref "U3") (pin "5") (pinfunction "C2-_5") (pintype "passive"))
    )
    (net (code "55") (name "Net-(U3-V+)") (class "Default")
      (node (ref "C10") (pin "2") (pinfunction "2_2") (pintype "passive"))
      (node (ref "U3") (pin "2") (pinfunction "V+_2") (pintype "power_in"))
    )
    (net (code "56") (name "Net-(U3-V-)") (class "Default")
      (node (ref "C11") (pin "2") (pinfunction "2_2") (pintype "passive"))
      (node (ref "U3") (pin "6") (pinfunction "V-_6") (pintype "power_in"))
    )
    (net (code "57") (name "Net-(U3-VCC)") (class "Default")
      (node (ref "C9") (pin "2") (pinfunction "2_2") (pintype "passive"))
      (node (ref "P6") (pin "2") (pinfunction "2_2") (pintype "passive"))
      (node (ref "U3") (pin "16") (pinfunction "VCC_16") (pintype "power_in"))
    )
    (net (code "58") (name "Net-(U4A-BOOT0)") (class "Default")
      (node (ref "R14") (pin "1") (pinfunction "1_1") (pintype "passive"))
      (node (ref "U4") (pin "60") (pinfunction "BOOT0_60") (pintype "input"))
    )
    (net (code "59") (name "Net-(U7-INPA)") (class "Default")
      (node (ref "C25") (pin "1") (pinfunction "1_1") (pintype "passive"))
      (node (ref "R11") (pin "2") (pinfunction "2_2") (pintype "passive"))
      (node (ref "U7") (pin "8") (pinfunction "INPA_8") (pintype "passive"))
    )
    (net (code "60") (name "Net-(U7-VBG)") (class "Default")
      (node (ref "C24") (pin "1") (pinfunction "1_1") (pintype "passive"))
      (node (ref "U7") (pin "6") (pinfunction "VBG_6") (pintype "passive"))
    )
    (net (code "61") (name "Net-(U7-VFB)") (class "Default")
      (node (ref "R12") (pin "1") (pinfunction "1_1") (pintype "passive"))
      (node (ref "R13") (pin "2") (pinfunction "2_2") (pintype "passive"))
      (node (ref "U7") (pin "4") (pinfunction "VFB_4") (pintype "passive"))
    )
    (net (code "62") (name "VCC3V3") (class "Default")
      (node (ref "C12") (pin "2") (pinfunction "2_2") (pintype "passive"))
      (node (ref "C13") (pin "2") (pinfunction "2_2") (pintype "passive"))
      (node (ref "C14") (pin "2") (pinfunction "2_2") (pintype "passive"))
      (node (ref "C15") (pin "2") (pinfunction "2_2") (pintype "passive"))
      (node (ref "C16") (pin "1") (pinfunction "1_1") (pintype "passive"))
      (node (ref "C17") (pin "1") (pinfunction "1_1") (pintype "passive"))
      (node (ref "C26") (pin "1") (pinfunction "1_1") (pintype "passive"))
      (node (ref "C5") (pin "1") (pinfunction "1_1") (pintype "passive"))
      (node (ref "C6") (pin "2") (pinfunction "2_2") (pintype "passive"))
      (node (ref "D3") (pin "A") (pinfunction "A_A") (pintype "passive"))
      (node (ref "D4") (pin "A") (pinfunction "A_A") (pintype "passive"))
      (node (ref "D5") (pin "A") (pinfunction "A_A") (pintype "passive"))
      (node (ref "D6") (pin "A") (pinfunction "A_A") (pintype "passive"))
      (node (ref "DB_232") (pin "1") (pinfunction "1_1") (pintype "passive"))
      (node (ref "DB_TTL") (pin "1") (pinfunction "1_1") (pintype "passive"))
      (node (ref "P6") (pin "1") (pinfunction "1_1") (pintype "passive"))
      (node (ref "Q3") (pin "2") (pinfunction "E_2") (pintype "passive"))
      (node (ref "R1") (pin "2") (pinfunction "2_2") (pintype "passive"))
      (node (ref "R2") (pin "2") (pinfunction "2_2") (pintype "passive"))
      (node (ref "SWD") (pin "4") (pinfunction "4_4") (pintype "passive"))
      (node (ref "U2") (pin "2") (pinfunction "VOUT_2") (pintype "passive"))
      (node (ref "U4") (pin "1") (pinfunction "VBAT_1") (pintype "power_in"))
      (node (ref "U4") (pin "13") (pinfunction "VDDA_13") (pintype "power_in"))
      (node (ref "U4") (pin "19") (pinfunction "VDD_4_19") (pintype "power_in"))
      (node (ref "U4") (pin "32") (pinfunction "VDD_1_32") (pintype "power_in"))
      (node (ref "U4") (pin "48") (pinfunction "VDD_2_48") (pintype "power_in"))
      (node (ref "U4") (pin "64") (pinfunction "VDD_3_64") (pintype "power_in"))
      (node (ref "U7") (pin "1") (pinfunction "VSUP_1") (pintype "passive"))
      (node (ref "U7") (pin "16") (pinfunction "DVDD_16") (pintype "passive"))
      (node (ref "U8") (pin "6") (pinfunction "C_6") (pintype "passive"))
      (node (ref "USART2") (pin "1") (pinfunction "1_1") (pintype "passive"))
    )
    (net (code "63") (name "VCC5V") (class "Default")
      (node (ref "C21") (pin "2") (pinfunction "2_2") (pintype "passive"))
      (node (ref "C28") (pin "2") (pinfunction "2_2") (pintype "passive"))
      (node (ref "C3") (pin "1") (pinfunction "1_1") (pintype "passive"))
      (node (ref "C4") (pin "2") (pinfunction "2_2") (pintype "passive"))
      (node (ref "L1") (pin "2") (pinfunction "2_2") (pintype "passive"))
      (node (ref "LS1") (pin "1") (pinfunction "A_1") (pintype "passive"))
      (node (ref "Light") (pin "1") (pinfunction "1_1") (pintype "passive"))
      (node (ref "PB3") (pin "1") (pinfunction "1_1") (pintype "passive"))
      (node (ref "PB4") (pin "1") (pinfunction "1_1") (pintype "passive"))
      (node (ref "PC12") (pin "1") (pinfunction "1_1") (pintype "passive"))
      (node (ref "PD2") (pin "1") (pinfunction "1_1") (pintype "passive"))
      (node (ref "U1") (pin "4") (pinfunction "FB_4") (pintype "input"))
      (node (ref "U2") (pin "3") (pinfunction "VIN_3") (pintype "passive"))
      (node (ref "U8") (pin "3") (pinfunction "A_3") (pintype "passive"))
      (node (ref "Wind1") (pin "1") (pinfunction "1_1") (pintype "passive"))
      (node (ref "Wind2") (pin "1") (pinfunction "1_1") (pintype "passive"))
    )
    (net (code "64") (name "VCC24V") (class "Default")
      (node (ref "C1") (pin "1") (pinfunction "1_1") (pintype "passive"))
      (node (ref "C2") (pin "2") (pinfunction "2_2") (pintype "passive"))
      (node (ref "Cir-Temp") (pin "1") (pinfunction "1_1") (pintype "passive"))
      (node (ref "S1") (pin "2") (pinfunction "NO_2") (pintype "passive"))
      (node (ref "U1") (pin "1") (pinfunction "IN_1") (pintype "power_in"))
      (node (ref "Water_temp1") (pin "1") (pinfunction "1_1") (pintype "passive"))
      (node (ref "Water_temp2") (pin "1") (pinfunction "1_1") (pintype "passive"))
    )
    (net (code "65") (name "unconnected-(U3-R2IN-Pad8)") (class "Default")
      (node (ref "U3") (pin "8") (pinfunction "R2IN_8") (pintype "input"))
    )
    (net (code "66") (name "unconnected-(U3-R2OUT-Pad9)") (class "Default")
      (node (ref "U3") (pin "9") (pinfunction "R2OUT_9") (pintype "output"))
    )
    (net (code "67") (name "unconnected-(U3-T2IN-Pad10)") (class "Default")
      (node (ref "U3") (pin "10") (pinfunction "T2IN_10") (pintype "input"))
    )
    (net (code "68") (name "unconnected-(U3-T2OUT-Pad7)") (class "Default")
      (node (ref "U3") (pin "7") (pinfunction "T2OUT_7") (pintype "output"))
    )
    (net (code "69") (name "unconnected-(U4A-PA0-WKUP-Pad14)") (class "Default")
      (node (ref "U4") (pin "14") (pinfunction "PA0-WKUP_14") (pintype "bidirectional"))
    )
    (net (code "70") (name "unconnected-(U4A-PA1-Pad15)") (class "Default")
      (node (ref "U4") (pin "15") (pinfunction "PA1_15") (pintype "bidirectional"))
    )
    (net (code "71") (name "unconnected-(U4A-PA2-Pad16)") (class "Default")
      (node (ref "U4") (pin "16") (pinfunction "PA2_16") (pintype "bidirectional"))
    )
    (net (code "72") (name "unconnected-(U4A-PA3-Pad17)") (class "Default")
      (node (ref "U4") (pin "17") (pinfunction "PA3_17") (pintype "bidirectional"))
    )
    (net (code "73") (name "unconnected-(U4A-PA8-Pad41)") (class "Default")
      (node (ref "U4") (pin "41") (pinfunction "PA8_41") (pintype "bidirectional"))
    )
    (net (code "74") (name "unconnected-(U4A-PA11-Pad44)") (class "Default")
      (node (ref "U4") (pin "44") (pinfunction "PA11_44") (pintype "bidirectional"))
    )
    (net (code "75") (name "unconnected-(U4A-PA12-Pad45)") (class "Default")
      (node (ref "U4") (pin "45") (pinfunction "PA12_45") (pintype "bidirectional"))
    )
    (net (code "76") (name "unconnected-(U4A-PB1-Pad27)") (class "Default")
      (node (ref "U4") (pin "27") (pinfunction "PB1_27") (pintype "bidirectional"))
    )
    (net (code "77") (name "unconnected-(U4A-PB2-Pad28)") (class "Default")
      (node (ref "U4") (pin "28") (pinfunction "PB2_28") (pintype "bidirectional"))
    )
    (net (code "78") (name "unconnected-(U4A-PB5-Pad57)") (class "Default")
      (node (ref "U4") (pin "57") (pinfunction "PB5_57") (pintype "bidirectional"))
    )
    (net (code "79") (name "unconnected-(U4A-PB6-Pad58)") (class "Default")
      (node (ref "U4") (pin "58") (pinfunction "PB6_58") (pintype "bidirectional"))
    )
    (net (code "80") (name "unconnected-(U4A-PB7-Pad59)") (class "Default")
      (node (ref "U4") (pin "59") (pinfunction "PB7_59") (pintype "bidirectional"))
    )
    (net (code "81") (name "unconnected-(U4A-PB8-Pad61)") (class "Default")
      (node (ref "U4") (pin "61") (pinfunction "PB8_61") (pintype "bidirectional"))
    )
    (net (code "82") (name "unconnected-(U4A-PC0-Pad8)") (class "Default")
      (node (ref "U4") (pin "8") (pinfunction "PC0_8") (pintype "bidirectional"))
    )
    (net (code "83") (name "unconnected-(U4A-PC1-Pad9)") (class "Default")
      (node (ref "U4") (pin "9") (pinfunction "PC1_9") (pintype "bidirectional"))
    )
    (net (code "84") (name "unconnected-(U4A-PC2-Pad10)") (class "Default")
      (node (ref "U4") (pin "10") (pinfunction "PC2_10") (pintype "bidirectional"))
    )
    (net (code "85") (name "unconnected-(U4A-PC3-Pad11)") (class "Default")
      (node (ref "U4") (pin "11") (pinfunction "PC3_11") (pintype "bidirectional"))
    )
    (net (code "86") (name "unconnected-(U4A-PC6-Pad37)") (class "Default")
      (node (ref "U4") (pin "37") (pinfunction "PC6_37") (pintype "bidirectional"))
    )
    (net (code "87") (name "unconnected-(U4A-PC7-Pad38)") (class "Default")
      (node (ref "U4") (pin "38") (pinfunction "PC7_38") (pintype "bidirectional"))
    )
    (net (code "88") (name "unconnected-(U4A-PC8-Pad39)") (class "Default")
      (node (ref "U4") (pin "39") (pinfunction "PC8_39") (pintype "bidirectional"))
    )
    (net (code "89") (name "unconnected-(U4A-PC9-Pad40)") (class "Default")
      (node (ref "U4") (pin "40") (pinfunction "PC9_40") (pintype "bidirectional"))
    )
    (net (code "90") (name "unconnected-(U4A-PC13-TAMPER-RTC-Pad2)") (class "Default")
      (node (ref "U4") (pin "2") (pinfunction "PC13-TAMPER-RTC_2") (pintype "bidirectional"))
    )
    (net (code "91") (name "unconnected-(U4A-PC14-OSC32_IN-Pad3)") (class "Default")
      (node (ref "U4") (pin "3") (pinfunction "PC14-OSC32_IN_3") (pintype "bidirectional"))
    )
    (net (code "92") (name "unconnected-(U4A-PC15-OSC32_OUT-Pad4)") (class "Default")
      (node (ref "U4") (pin "4") (pinfunction "PC15-OSC32_OUT_4") (pintype "bidirectional"))
    )
    (net (code "93") (name "unconnected-(U7-INNB-Pad9)") (class "Default")
      (node (ref "U7") (pin "9") (pinfunction "INNB_9") (pintype "passive"))
    )
    (net (code "94") (name "unconnected-(U7-INPB-Pad10)") (class "Default")
      (node (ref "U7") (pin "10") (pinfunction "INPB_10") (pintype "passive"))
    )
    (net (code "95") (name "unconnected-(U7-XO-Pad13)") (class "Default")
      (node (ref "U7") (pin "13") (pinfunction "XO_13") (pintype "passive"))
    )
    (net (code "96") (name "unconnected-(U8-A-Pad1)") (class "Default")
      (node (ref "U8") (pin "1") (pinfunction "A_1") (pintype "passive"))
    )
    (net (code "97") (name "unconnected-(U8-C-Pad8)") (class "Default")
      (node (ref "U8") (pin "8") (pinfunction "C_8") (pintype "passive"))
    )
    (net (code "98") (name "unconnected-(U8-E-Pad7)") (class "Default")
      (node (ref "U8") (pin "7") (pinfunction "E_7") (pintype "passive"))
    )
    (net (code "99") (name "unconnected-(U8-K-Pad2)") (class "Default")
      (node (ref "U8") (pin "2") (pinfunction "K_2") (pintype "passive"))
    )
  )
)
